# Daughterboard.net
KiCad netlist of a schematic drawn in Altium Designer
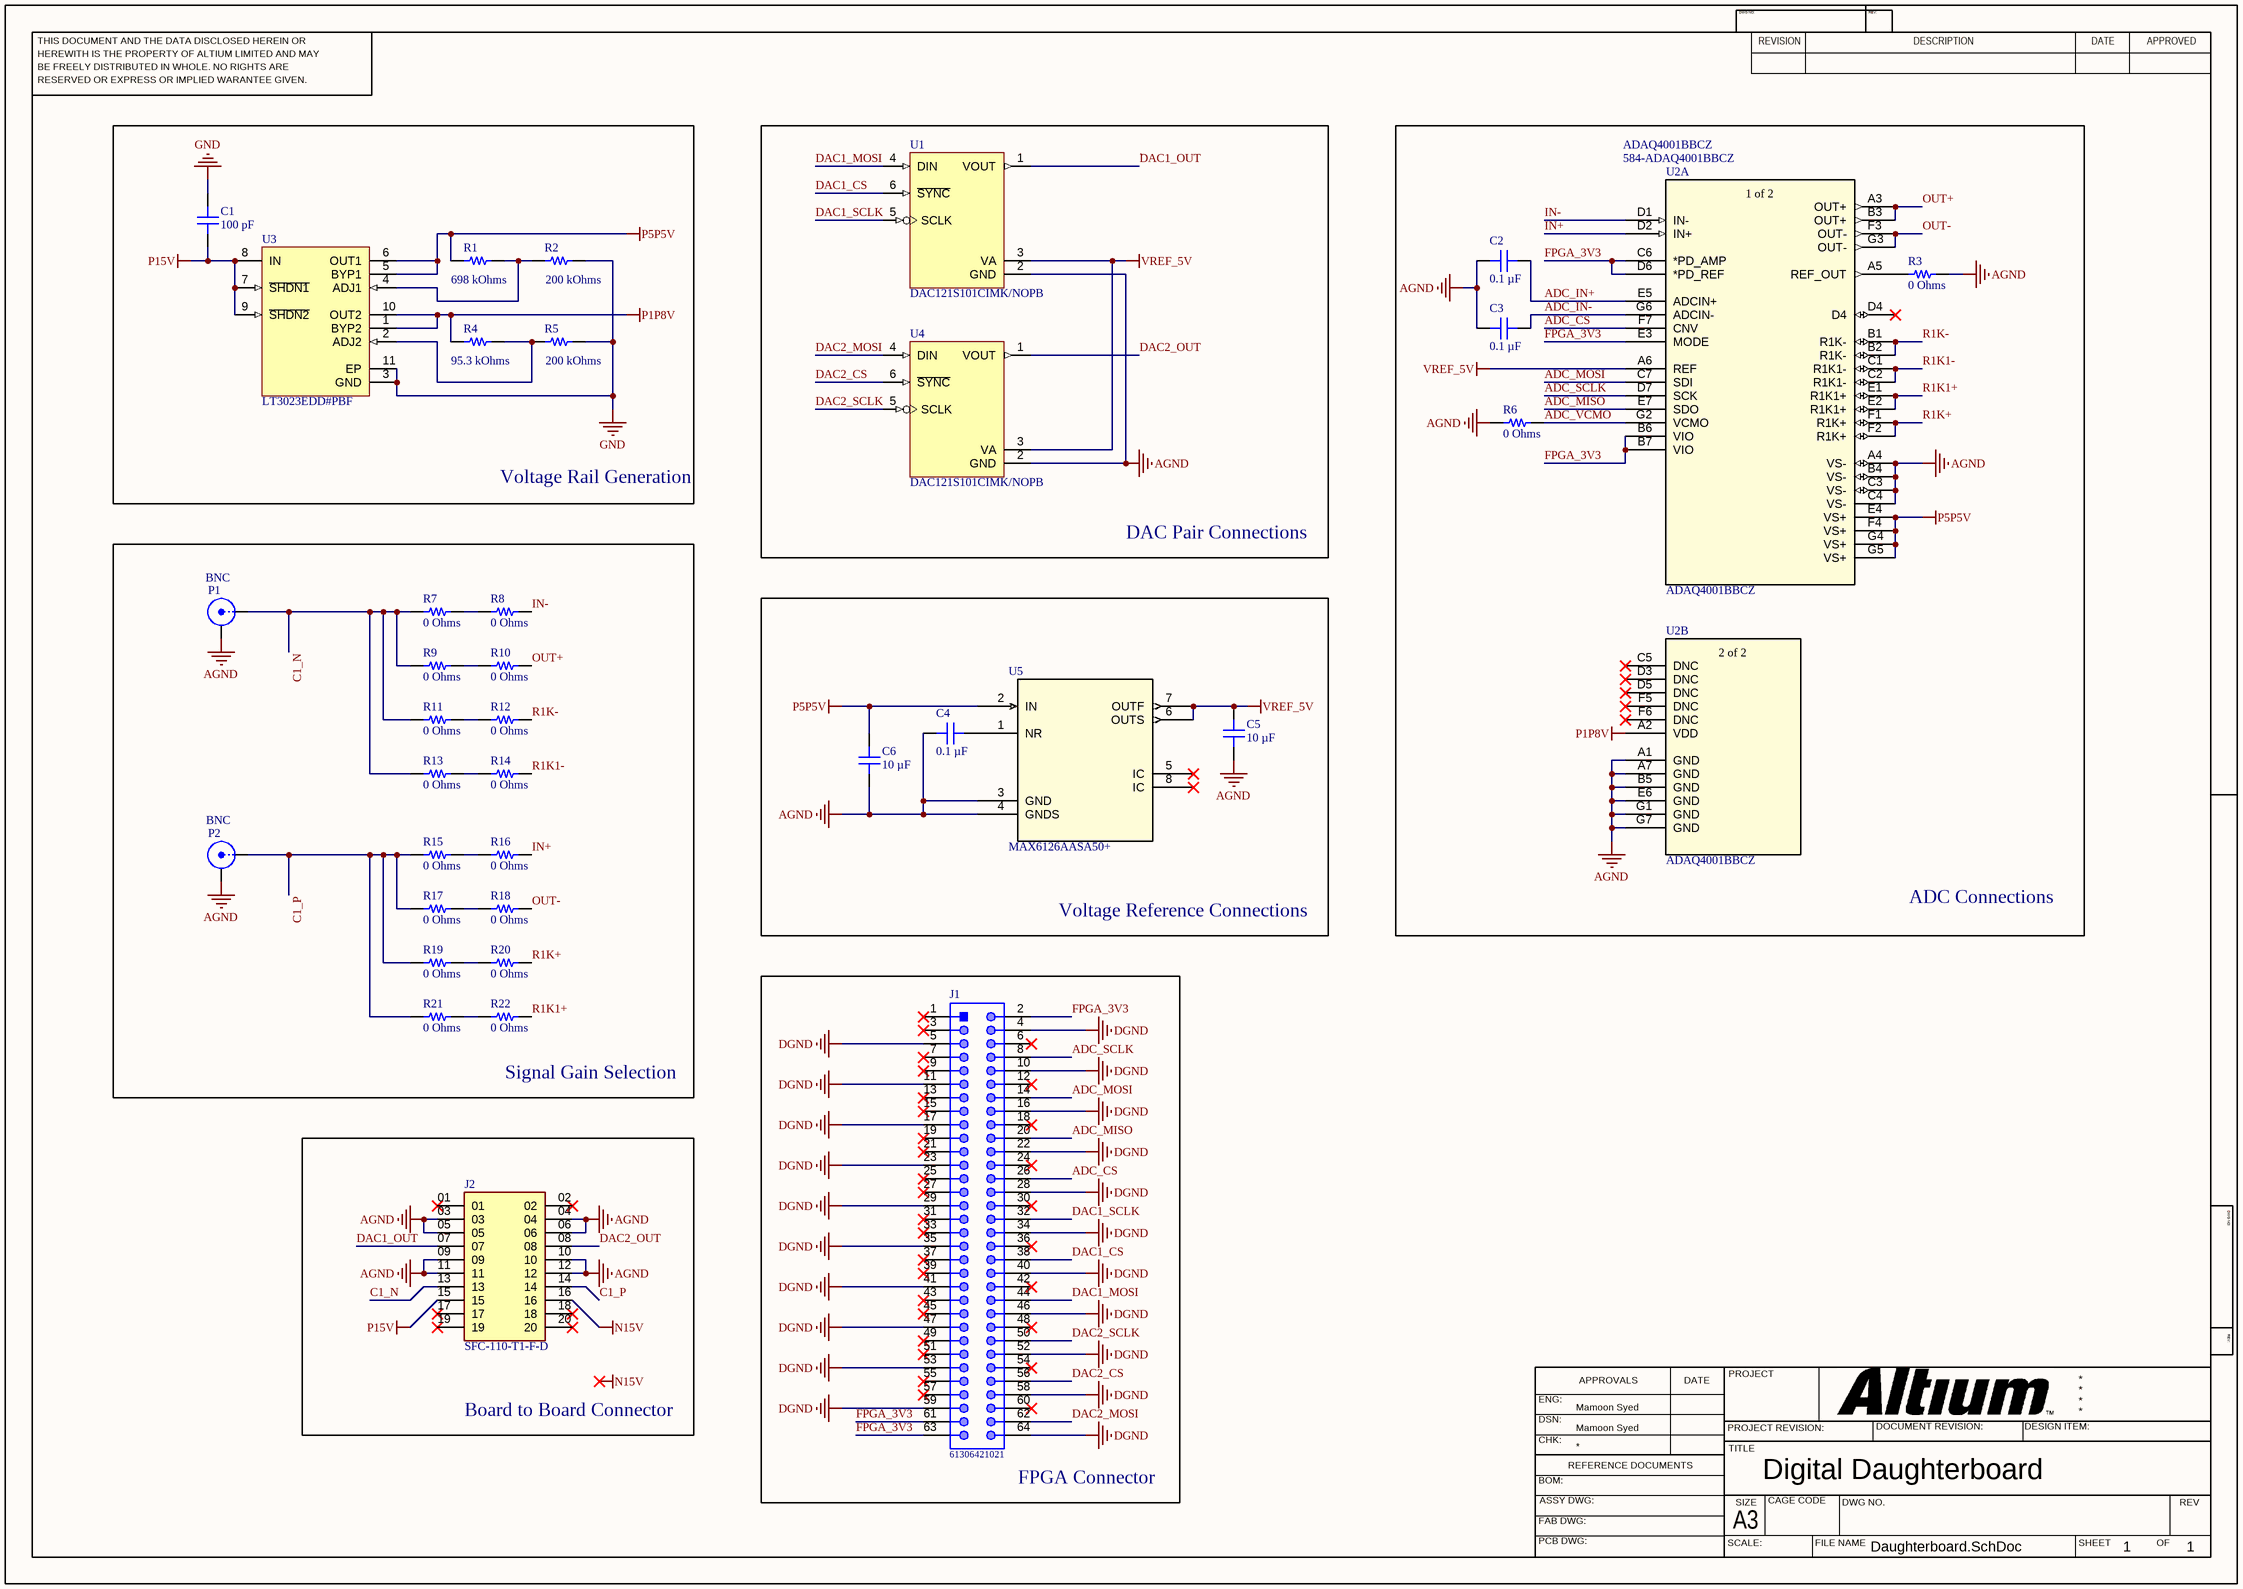
[diagram p0: Daughterboard.SchDoc]

(export (version "E")
  (design (tool "Eeschema 10.0.6"))
  (components
    (comp (ref "C1")
      (value "100 pF")
      (footprint "CAP 0603_1608")
      (description "CAP CER 100PF 50V C0G/NP0 0603")
      (fields (field (name "PART NUMBER") "C0603C101K5GACAUTO") (field (name "MANUFACTURER") "KEMET"))
      (libsource (lib "Celestial Altium Library - altium_library") (part "Capacitor"))
    )
    (comp (ref "C2")
      (value "0.1 µF")
      (footprint "CAP 0603_1608")
      (description "CAP CER 0.1UF 50V X7R 0603")
      (fields (field (name "PART NUMBER") "C0603C104K5RAC7411") (field (name "MANUFACTURER") "KEMET"))
      (libsource (lib "Celestial Altium Library - altium_library") (part "Capacitor"))
    )
    (comp (ref "C3")
      (value "0.1 µF")
      (footprint "CAP 0603_1608")
      (description "CAP CER 0.1UF 50V X7R 0603")
      (fields (field (name "PART NUMBER") "C0603C104K5RAC7411") (field (name "MANUFACTURER") "KEMET"))
      (libsource (lib "Celestial Altium Library - altium_library") (part "Capacitor"))
    )
    (comp (ref "C4")
      (value "0.1 µF")
      (footprint "CAP 0603_1608")
      (description "CAP CER 0.1UF 50V X7R 0603")
      (fields (field (name "PART NUMBER") "C0603C104K5RAC7411") (field (name "MANUFACTURER") "KEMET"))
      (libsource (lib "Celestial Altium Library - altium_library") (part "Capacitor"))
    )
    (comp (ref "C5")
      (value "10 µF")
      (footprint "CAP 0603_1608")
      (description "CAP CER 10UF 6.3V X5R 0603")
      (fields
        (field (name "PART NUMBER") "GRM188R60J106ME47D")
        (field (name "MANUFACTURER") "Murata Electronics")
      )
      (libsource (lib "Celestial Altium Library - altium_library") (part "Capacitor"))
    )
    (comp (ref "C6")
      (value "10 µF")
      (footprint "CAP 0603_1608")
      (description "CAP CER 10UF 6.3V X5R 0603")
      (fields
        (field (name "PART NUMBER") "GRM188R60J106ME47D")
        (field (name "MANUFACTURER") "Murata Electronics")
      )
      (libsource (lib "Celestial Altium Library - altium_library") (part "Capacitor"))
    )
    (comp (ref "J1")
      (value "61306421021")
      (footprint "61306421021")
      (description "THT Angled Pin Header WR-PHD, Pitch 2.54 mm, Dual Row, 64 pins")
      (fields (field (name "MANUFACTURER") "Wurth Elektronik") (field (name "PUBLISHER") "WurthElektronik"))
      (libsource (lib "Altium Content Vault") (part "WE-CN-2P-M-R64"))
    )
    (comp (ref "J2")
      (value "SFC-110-T1-F-D")
      (footprint "SAMTEC_SFC-110-T1-F-D")
      (libsource (lib "SFC-110-T1-F-D") (part "SFC-110-T1-F-D"))
    )
    (comp (ref "P1")
      (value "BNC")
      (footprint "BNC_RA CON")
      (description "BNC Elbow Connector")
      (fields (field (name "PUBLISHER") "Altium Limited"))
      (libsource (lib "Miscellaneous Connectors") (part "BNC"))
    )
    (comp (ref "P2")
      (value "BNC")
      (footprint "BNC_RA CON")
      (description "BNC Elbow Connector")
      (fields (field (name "PUBLISHER") "Altium Limited"))
      (libsource (lib "Miscellaneous Connectors") (part "BNC"))
    )
    (comp (ref "R1")
      (value "698 kOhms")
      (footprint "RES 0603_1608")
      (description "RES 698K OHM 1% 1/10W 0603")
      (fields (field (name "PART NUMBER") "RC0603FR-07698KL") (field (name "MANUFACTURER") "Yageo"))
      (libsource (lib "Celestial Altium Library - altium_library") (part "Resistor"))
    )
    (comp (ref "R2")
      (value "200 kOhms")
      (footprint "RES 0603_1608")
      (description "RES 200K OHM 5% 1/10W 0603")
      (fields
        (field (name "PART NUMBER") "RK73B1JTTD204J")
        (field (name "MANUFACTURER") "KOA Speer Electronics, Inc.")
      )
      (libsource (lib "Celestial Altium Library - altium_library") (part "Resistor"))
    )
    (comp (ref "R3")
      (value "0 Ohms")
      (footprint "RES 0603_1608")
      (description "RES SMD 0 OHM JUMPER 1/10W 0603")
      (fields (field (name "PART NUMBER") "AC0603JR-070RL") (field (name "MANUFACTURER") "Yageo"))
      (libsource (lib "Celestial Altium Library - altium_library") (part "Resistor"))
    )
    (comp (ref "R4")
      (value "95.3 kOhms")
      (footprint "RES 0603_1608")
      (description "RES 95.3K OHM 1% 1/10W 0603")
      (fields (field (name "PART NUMBER") "RC0603FR-0795K3L") (field (name "MANUFACTURER") "Yageo"))
      (libsource (lib "Celestial Altium Library - altium_library") (part "Resistor"))
    )
    (comp (ref "R5")
      (value "200 kOhms")
      (footprint "RES 0603_1608")
      (description "RES 200K OHM 5% 1/10W 0603")
      (fields
        (field (name "PART NUMBER") "RK73B1JTTD204J")
        (field (name "MANUFACTURER") "KOA Speer Electronics, Inc.")
      )
      (libsource (lib "Celestial Altium Library - altium_library") (part "Resistor"))
    )
    (comp (ref "R6")
      (value "0 Ohms")
      (footprint "RES 0603_1608")
      (description "RES SMD 0 OHM JUMPER 1/10W 0603")
      (fields (field (name "PART NUMBER") "AC0603JR-070RL") (field (name "MANUFACTURER") "Yageo"))
      (libsource (lib "Celestial Altium Library - altium_library") (part "Resistor"))
    )
    (comp (ref "R7")
      (value "0 Ohms")
      (footprint "RES 0603_1608")
      (description "RES SMD 0 OHM JUMPER 1/10W 0603")
      (fields (field (name "PART NUMBER") "AC0603JR-070RL") (field (name "MANUFACTURER") "Yageo"))
      (libsource (lib "Celestial Altium Library - altium_library") (part "Resistor"))
    )
    (comp (ref "R8")
      (value "0 Ohms")
      (footprint "RES 0603_1608")
      (description "RES SMD 0 OHM JUMPER 1/10W 0603")
      (fields (field (name "PART NUMBER") "AC0603JR-070RL") (field (name "MANUFACTURER") "Yageo"))
      (libsource (lib "Celestial Altium Library - altium_library") (part "Resistor"))
    )
    (comp (ref "R9")
      (value "0 Ohms")
      (footprint "RES 0603_1608")
      (description "RES SMD 0 OHM JUMPER 1/10W 0603")
      (fields (field (name "PART NUMBER") "AC0603JR-070RL") (field (name "MANUFACTURER") "Yageo"))
      (libsource (lib "Celestial Altium Library - altium_library") (part "Resistor"))
    )
    (comp (ref "R10")
      (value "0 Ohms")
      (footprint "RES 0603_1608")
      (description "RES SMD 0 OHM JUMPER 1/10W 0603")
      (fields (field (name "PART NUMBER") "AC0603JR-070RL") (field (name "MANUFACTURER") "Yageo"))
      (libsource (lib "Celestial Altium Library - altium_library") (part "Resistor"))
    )
    (comp (ref "R11")
      (value "0 Ohms")
      (footprint "RES 0603_1608")
      (description "RES SMD 0 OHM JUMPER 1/10W 0603")
      (fields (field (name "PART NUMBER") "AC0603JR-070RL") (field (name "MANUFACTURER") "Yageo"))
      (libsource (lib "Celestial Altium Library - altium_library") (part "Resistor"))
    )
    (comp (ref "R12")
      (value "0 Ohms")
      (footprint "RES 0603_1608")
      (description "RES SMD 0 OHM JUMPER 1/10W 0603")
      (fields (field (name "PART NUMBER") "AC0603JR-070RL") (field (name "MANUFACTURER") "Yageo"))
      (libsource (lib "Celestial Altium Library - altium_library") (part "Resistor"))
    )
    (comp (ref "R13")
      (value "0 Ohms")
      (footprint "RES 0603_1608")
      (description "RES SMD 0 OHM JUMPER 1/10W 0603")
      (fields (field (name "PART NUMBER") "AC0603JR-070RL") (field (name "MANUFACTURER") "Yageo"))
      (libsource (lib "Celestial Altium Library - altium_library") (part "Resistor"))
    )
    (comp (ref "R14")
      (value "0 Ohms")
      (footprint "RES 0603_1608")
      (description "RES SMD 0 OHM JUMPER 1/10W 0603")
      (fields (field (name "PART NUMBER") "AC0603JR-070RL") (field (name "MANUFACTURER") "Yageo"))
      (libsource (lib "Celestial Altium Library - altium_library") (part "Resistor"))
    )
    (comp (ref "R15")
      (value "0 Ohms")
      (footprint "RES 0603_1608")
      (description "RES SMD 0 OHM JUMPER 1/10W 0603")
      (fields (field (name "PART NUMBER") "AC0603JR-070RL") (field (name "MANUFACTURER") "Yageo"))
      (libsource (lib "Celestial Altium Library - altium_library") (part "Resistor"))
    )
    (comp (ref "R16")
      (value "0 Ohms")
      (footprint "RES 0603_1608")
      (description "RES SMD 0 OHM JUMPER 1/10W 0603")
      (fields (field (name "PART NUMBER") "AC0603JR-070RL") (field (name "MANUFACTURER") "Yageo"))
      (libsource (lib "Celestial Altium Library - altium_library") (part "Resistor"))
    )
    (comp (ref "R17")
      (value "0 Ohms")
      (footprint "RES 0603_1608")
      (description "RES SMD 0 OHM JUMPER 1/10W 0603")
      (fields (field (name "PART NUMBER") "AC0603JR-070RL") (field (name "MANUFACTURER") "Yageo"))
      (libsource (lib "Celestial Altium Library - altium_library") (part "Resistor"))
    )
    (comp (ref "R18")
      (value "0 Ohms")
      (footprint "RES 0603_1608")
      (description "RES SMD 0 OHM JUMPER 1/10W 0603")
      (fields (field (name "PART NUMBER") "AC0603JR-070RL") (field (name "MANUFACTURER") "Yageo"))
      (libsource (lib "Celestial Altium Library - altium_library") (part "Resistor"))
    )
    (comp (ref "R19")
      (value "0 Ohms")
      (footprint "RES 0603_1608")
      (description "RES SMD 0 OHM JUMPER 1/10W 0603")
      (fields (field (name "PART NUMBER") "AC0603JR-070RL") (field (name "MANUFACTURER") "Yageo"))
      (libsource (lib "Celestial Altium Library - altium_library") (part "Resistor"))
    )
    (comp (ref "R20")
      (value "0 Ohms")
      (footprint "RES 0603_1608")
      (description "RES SMD 0 OHM JUMPER 1/10W 0603")
      (fields (field (name "PART NUMBER") "AC0603JR-070RL") (field (name "MANUFACTURER") "Yageo"))
      (libsource (lib "Celestial Altium Library - altium_library") (part "Resistor"))
    )
    (comp (ref "R21")
      (value "0 Ohms")
      (footprint "RES 0603_1608")
      (description "RES SMD 0 OHM JUMPER 1/10W 0603")
      (fields (field (name "PART NUMBER") "AC0603JR-070RL") (field (name "MANUFACTURER") "Yageo"))
      (libsource (lib "Celestial Altium Library - altium_library") (part "Resistor"))
    )
    (comp (ref "R22")
      (value "0 Ohms")
      (footprint "RES 0603_1608")
      (description "RES SMD 0 OHM JUMPER 1/10W 0603")
      (fields (field (name "PART NUMBER") "AC0603JR-070RL") (field (name "MANUFACTURER") "Yageo"))
      (libsource (lib "Celestial Altium Library - altium_library") (part "Resistor"))
    )
    (comp (ref "U1")
      (value "DAC121S101CIMK/NOPB")
      (footprint "MK06A_N")
      (description "12-Bit Micro Power, RRO Digital-to-Analog Converter, 6-pin Tiny SOT23, Pb-Free")
      (fields (field (name "MANUFACTURER") "National Semiconductor"))
      (libsource (lib "Altium Content Vault") (part "CON-DAC-DAC121S101-6"))
    )
    (comp (ref "U2")
      (value "ADAQ4001BBCZ")
      (footprint "BGA49_ADAQ4001BBCZ_ADI")
      (description "Analog Devices ADAQ4001 - 16-Bit Sequential Approximation ADC")
      (fields
        (field (name "SUPPLIER PART NUMBER 1") "584-ADAQ4001BBCZ")
        (field (name "SUPPLIER PART NUMBER 2") "ADAQ4001BBCZ")
        (field (name "COPYRIGHT") "Copyright (C) 2022 Ultra Librarian. All rights reserved.")
      )
      (libsource (lib "ADAQ4001BBCZ") (part "ADAQ4001BBCZ"))
    )
    (comp (ref "U3")
      (value "LT3023EDD#PBF")
      (footprint "LT-DD-10_V")
      (fields (field (name "MANUFACTURER") "Linear Technology"))
      (libsource (lib "Altium Content Vault") (part "LT-LT3023-X-10-X"))
    )
    (comp (ref "U4")
      (value "DAC121S101CIMK/NOPB")
      (footprint "MK06A_N")
      (description "12-Bit Micro Power, RRO Digital-to-Analog Converter, 6-pin Tiny SOT23, Pb-Free")
      (fields (field (name "MANUFACTURER") "National Semiconductor"))
      (libsource (lib "Altium Content Vault") (part "CON-DAC-DAC121S101-6"))
    )
    (comp (ref "U5")
      (value "MAX6126AASA50+")
      (footprint "21-0041B_8")
      (description "MAX6126AASA50+ Voltage Reference")
      (fields (field (name "COPYRIGHT") "Copyright (C) 2022 Ultra Librarian. All rights reserved."))
      (libsource (lib "MAX6126AASA50&plus_") (part "MAX6126AASA50+"))
    )
  )
  (nets
    (net (code "1") (name "/ADC_CS") (class "Default")
      (node (ref "J1") (pin "26") (pinfunction "26_26") (pintype "passive"))
      (node (ref "U2") (pin "F7") (pinfunction "CNV_F7") (pintype "passive"))
    )
    (net (code "2") (name "/ADC_IN+") (class "Default")
      (node (ref "C2") (pin "2") (pinfunction "2_2") (pintype "passive"))
      (node (ref "U2") (pin "E5") (pinfunction "ADCIN+_E5") (pintype "passive"))
    )
    (net (code "3") (name "/ADC_IN-") (class "Default")
      (node (ref "C3") (pin "2") (pinfunction "2_2") (pintype "passive"))
      (node (ref "U2") (pin "G6") (pinfunction "ADCIN-_G6") (pintype "passive"))
    )
    (net (code "4") (name "/ADC_MISO") (class "Default")
      (node (ref "J1") (pin "20") (pinfunction "20_20") (pintype "passive"))
      (node (ref "U2") (pin "E7") (pinfunction "SDO_E7") (pintype "passive"))
    )
    (net (code "5") (name "/ADC_MOSI") (class "Default")
      (node (ref "J1") (pin "14") (pinfunction "14_14") (pintype "passive"))
      (node (ref "U2") (pin "C7") (pinfunction "SDI_C7") (pintype "passive"))
    )
    (net (code "6") (name "/ADC_SCLK") (class "Default")
      (node (ref "J1") (pin "8") (pinfunction "8_8") (pintype "passive"))
      (node (ref "U2") (pin "D7") (pinfunction "SCK_D7") (pintype "passive"))
    )
    (net (code "7") (name "/ADC_VCMO") (class "Default")
      (node (ref "R6") (pin "2") (pinfunction "2_2") (pintype "passive"))
      (node (ref "U2") (pin "G2") (pinfunction "VCMO_G2") (pintype "passive"))
    )
    (net (code "8") (name "/C1_N") (class "Default")
      (node (ref "J2") (pin "13") (pinfunction "13_13") (pintype "passive"))
      (node (ref "P1") (pin "1") (pinfunction "X_1") (pintype "passive"))
      (node (ref "R11") (pin "1") (pinfunction "1_1") (pintype "passive"))
      (node (ref "R13") (pin "1") (pinfunction "1_1") (pintype "passive"))
      (node (ref "R7") (pin "1") (pinfunction "1_1") (pintype "passive"))
      (node (ref "R9") (pin "1") (pinfunction "1_1") (pintype "passive"))
    )
    (net (code "9") (name "/C1_P") (class "Default")
      (node (ref "J2") (pin "14") (pinfunction "14_14") (pintype "passive"))
      (node (ref "P2") (pin "1") (pinfunction "X_1") (pintype "passive"))
      (node (ref "R15") (pin "1") (pinfunction "1_1") (pintype "passive"))
      (node (ref "R17") (pin "1") (pinfunction "1_1") (pintype "passive"))
      (node (ref "R19") (pin "1") (pinfunction "1_1") (pintype "passive"))
      (node (ref "R21") (pin "1") (pinfunction "1_1") (pintype "passive"))
    )
    (net (code "10") (name "/DAC1_CS") (class "Default")
      (node (ref "J1") (pin "38") (pinfunction "38_38") (pintype "passive"))
      (node (ref "U1") (pin "6") (pinfunction "~{SYNC}_6") (pintype "input"))
    )
    (net (code "11") (name "/DAC1_MOSI") (class "Default")
      (node (ref "J1") (pin "44") (pinfunction "44_44") (pintype "passive"))
      (node (ref "U1") (pin "4") (pinfunction "DIN_4") (pintype "input"))
    )
    (net (code "12") (name "/DAC1_OUT") (class "Default")
      (node (ref "J2") (pin "07") (pinfunction "07_07") (pintype "passive"))
      (node (ref "U1") (pin "1") (pinfunction "VOUT_1") (pintype "output"))
    )
    (net (code "13") (name "/DAC1_SCLK") (class "Default")
      (node (ref "J1") (pin "32") (pinfunction "32_32") (pintype "passive"))
      (node (ref "U1") (pin "5") (pinfunction "SCLK_5") (pintype "input"))
    )
    (net (code "14") (name "/DAC2_CS") (class "Default")
      (node (ref "J1") (pin "56") (pinfunction "56_56") (pintype "passive"))
      (node (ref "U4") (pin "6") (pinfunction "~{SYNC}_6") (pintype "input"))
    )
    (net (code "15") (name "/DAC2_MOSI") (class "Default")
      (node (ref "J1") (pin "62") (pinfunction "62_62") (pintype "passive"))
      (node (ref "U4") (pin "4") (pinfunction "DIN_4") (pintype "input"))
    )
    (net (code "16") (name "/DAC2_OUT") (class "Default")
      (node (ref "J2") (pin "08") (pinfunction "08_08") (pintype "passive"))
      (node (ref "U4") (pin "1") (pinfunction "VOUT_1") (pintype "output"))
    )
    (net (code "17") (name "/DAC2_SCLK") (class "Default")
      (node (ref "J1") (pin "50") (pinfunction "50_50") (pintype "passive"))
      (node (ref "U4") (pin "5") (pinfunction "SCLK_5") (pintype "input"))
    )
    (net (code "18") (name "/FPGA_3V3") (class "Default")
      (node (ref "J1") (pin "2") (pinfunction "2_2") (pintype "passive"))
      (node (ref "J1") (pin "61") (pinfunction "61_61") (pintype "passive"))
      (node (ref "J1") (pin "63") (pinfunction "63_63") (pintype "passive"))
      (node (ref "U2") (pin "B6") (pinfunction "VIO_B6") (pintype "passive"))
      (node (ref "U2") (pin "B7") (pinfunction "VIO_B7") (pintype "passive"))
      (node (ref "U2") (pin "C6") (pinfunction "*PD_AMP_C6") (pintype "passive"))
      (node (ref "U2") (pin "D6") (pinfunction "*PD_REF_D6") (pintype "passive"))
      (node (ref "U2") (pin "E3") (pinfunction "MODE_E3") (pintype "passive"))
    )
    (net (code "19") (name "/IN+") (class "Default")
      (node (ref "R16") (pin "2") (pinfunction "2_2") (pintype "passive"))
      (node (ref "U2") (pin "D2") (pinfunction "IN+_D2") (pintype "input"))
    )
    (net (code "20") (name "/IN-") (class "Default")
      (node (ref "R8") (pin "2") (pinfunction "2_2") (pintype "passive"))
      (node (ref "U2") (pin "D1") (pinfunction "IN-_D1") (pintype "input"))
    )
    (net (code "21") (name "/OUT+") (class "Default")
      (node (ref "R10") (pin "2") (pinfunction "2_2") (pintype "passive"))
      (node (ref "U2") (pin "A3") (pinfunction "OUT+_A3") (pintype "output"))
      (node (ref "U2") (pin "B3") (pinfunction "OUT+_B3") (pintype "output"))
    )
    (net (code "22") (name "/OUT-") (class "Default")
      (node (ref "R18") (pin "2") (pinfunction "2_2") (pintype "passive"))
      (node (ref "U2") (pin "F3") (pinfunction "OUT-_F3") (pintype "output"))
      (node (ref "U2") (pin "G3") (pinfunction "OUT-_G3") (pintype "output"))
    )
    (net (code "23") (name "/R1K+") (class "Default")
      (node (ref "R20") (pin "2") (pinfunction "2_2") (pintype "passive"))
      (node (ref "U2") (pin "F1") (pinfunction "R1K+_F1") (pintype "bidirectional"))
      (node (ref "U2") (pin "F2") (pinfunction "R1K+_F2") (pintype "bidirectional"))
    )
    (net (code "24") (name "/R1K-") (class "Default")
      (node (ref "R12") (pin "2") (pinfunction "2_2") (pintype "passive"))
      (node (ref "U2") (pin "B1") (pinfunction "R1K-_B1") (pintype "bidirectional"))
      (node (ref "U2") (pin "B2") (pinfunction "R1K-_B2") (pintype "bidirectional"))
    )
    (net (code "25") (name "/R1K1+") (class "Default")
      (node (ref "R22") (pin "2") (pinfunction "2_2") (pintype "passive"))
      (node (ref "U2") (pin "E1") (pinfunction "R1K1+_E1") (pintype "bidirectional"))
      (node (ref "U2") (pin "E2") (pinfunction "R1K1+_E2") (pintype "bidirectional"))
    )
    (net (code "26") (name "/R1K1-") (class "Default")
      (node (ref "R14") (pin "2") (pinfunction "2_2") (pintype "passive"))
      (node (ref "U2") (pin "C1") (pinfunction "R1K1-_C1") (pintype "bidirectional"))
      (node (ref "U2") (pin "C2") (pinfunction "R1K1-_C2") (pintype "bidirectional"))
    )
    (net (code "27") (name "AGND") (class "Default")
      (node (ref "C2") (pin "1") (pinfunction "1_1") (pintype "passive"))
      (node (ref "C3") (pin "1") (pinfunction "1_1") (pintype "passive"))
      (node (ref "C4") (pin "1") (pinfunction "1_1") (pintype "passive"))
      (node (ref "C5") (pin "1") (pinfunction "1_1") (pintype "passive"))
      (node (ref "C6") (pin "1") (pinfunction "1_1") (pintype "passive"))
      (node (ref "J2") (pin "03") (pinfunction "03_03") (pintype "passive"))
      (node (ref "J2") (pin "04") (pinfunction "04_04") (pintype "passive"))
      (node (ref "J2") (pin "05") (pinfunction "05_05") (pintype "passive"))
      (node (ref "J2") (pin "06") (pinfunction "06_06") (pintype "passive"))
      (node (ref "J2") (pin "09") (pinfunction "09_09") (pintype "passive"))
      (node (ref "J2") (pin "10") (pinfunction "10_10") (pintype "passive"))
      (node (ref "J2") (pin "11") (pinfunction "11_11") (pintype "passive"))
      (node (ref "J2") (pin "12") (pinfunction "12_12") (pintype "passive"))
      (node (ref "P1") (pin "2") (pinfunction "Y_2") (pintype "passive"))
      (node (ref "P2") (pin "2") (pinfunction "Y_2") (pintype "passive"))
      (node (ref "R3") (pin "2") (pinfunction "2_2") (pintype "passive"))
      (node (ref "R6") (pin "1") (pinfunction "1_1") (pintype "passive"))
      (node (ref "U1") (pin "2") (pinfunction "GND_2") (pintype "power_in"))
      (node (ref "U2") (pin "A1") (pinfunction "GND_A1") (pintype "passive"))
      (node (ref "U2") (pin "A4") (pinfunction "VS-_A4") (pintype "bidirectional"))
      (node (ref "U2") (pin "A7") (pinfunction "GND_A7") (pintype "passive"))
      (node (ref "U2") (pin "B4") (pinfunction "VS-_B4") (pintype "bidirectional"))
      (node (ref "U2") (pin "B5") (pinfunction "GND_B5") (pintype "passive"))
      (node (ref "U2") (pin "C3") (pinfunction "VS-_C3") (pintype "bidirectional"))
      (node (ref "U2") (pin "C4") (pinfunction "VS-_C4") (pintype "passive"))
      (node (ref "U2") (pin "E6") (pinfunction "GND_E6") (pintype "passive"))
      (node (ref "U2") (pin "G1") (pinfunction "GND_G1") (pintype "passive"))
      (node (ref "U2") (pin "G7") (pinfunction "GND_G7") (pintype "passive"))
      (node (ref "U4") (pin "2") (pinfunction "GND_2") (pintype "power_in"))
      (node (ref "U5") (pin "3") (pinfunction "GND_3") (pintype "power_in"))
      (node (ref "U5") (pin "4") (pinfunction "GNDS_4") (pintype "power_in"))
    )
    (net (code "28") (name "DGND") (class "Default")
      (node (ref "J1") (pin "10") (pinfunction "10_10") (pintype "passive"))
      (node (ref "J1") (pin "11") (pinfunction "11_11") (pintype "passive"))
      (node (ref "J1") (pin "16") (pinfunction "16_16") (pintype "passive"))
      (node (ref "J1") (pin "17") (pinfunction "17_17") (pintype "passive"))
      (node (ref "J1") (pin "22") (pinfunction "22_22") (pintype "passive"))
      (node (ref "J1") (pin "23") (pinfunction "23_23") (pintype "passive"))
      (node (ref "J1") (pin "28") (pinfunction "28_28") (pintype "passive"))
      (node (ref "J1") (pin "29") (pinfunction "29_29") (pintype "passive"))
      (node (ref "J1") (pin "34") (pinfunction "34_34") (pintype "passive"))
      (node (ref "J1") (pin "35") (pinfunction "35_35") (pintype "passive"))
      (node (ref "J1") (pin "4") (pinfunction "4_4") (pintype "passive"))
      (node (ref "J1") (pin "40") (pinfunction "40_40") (pintype "passive"))
      (node (ref "J1") (pin "41") (pinfunction "41_41") (pintype "passive"))
      (node (ref "J1") (pin "46") (pinfunction "46_46") (pintype "passive"))
      (node (ref "J1") (pin "47") (pinfunction "47_47") (pintype "passive"))
      (node (ref "J1") (pin "5") (pinfunction "5_5") (pintype "passive"))
      (node (ref "J1") (pin "52") (pinfunction "52_52") (pintype "passive"))
      (node (ref "J1") (pin "53") (pinfunction "53_53") (pintype "passive"))
      (node (ref "J1") (pin "58") (pinfunction "58_58") (pintype "passive"))
      (node (ref "J1") (pin "59") (pinfunction "59_59") (pintype "passive"))
      (node (ref "J1") (pin "64") (pinfunction "64_64") (pintype "passive"))
    )
    (net (code "29") (name "GND") (class "Default")
      (node (ref "C1") (pin "2") (pinfunction "2_2") (pintype "passive"))
      (node (ref "R2") (pin "2") (pinfunction "2_2") (pintype "passive"))
      (node (ref "R5") (pin "2") (pinfunction "2_2") (pintype "passive"))
      (node (ref "U3") (pin "11") (pinfunction "EP_11") (pintype "power_in"))
      (node (ref "U3") (pin "3") (pinfunction "GND_3") (pintype "power_in"))
    )
    (net (code "30") (name "N15V") (class "Default")
      (node (ref "J2") (pin "16") (pinfunction "16_16") (pintype "passive"))
    )
    (net (code "31") (name "Net-(R7-Pad2)") (class "Default")
      (node (ref "R7") (pin "2") (pinfunction "2_2") (pintype "passive"))
      (node (ref "R8") (pin "1") (pinfunction "1_1") (pintype "passive"))
    )
    (net (code "32") (name "Net-(R10-Pad1)") (class "Default")
      (node (ref "R10") (pin "1") (pinfunction "1_1") (pintype "passive"))
      (node (ref "R9") (pin "2") (pinfunction "2_2") (pintype "passive"))
    )
    (net (code "33") (name "Net-(R11-Pad2)") (class "Default")
      (node (ref "R11") (pin "2") (pinfunction "2_2") (pintype "passive"))
      (node (ref "R12") (pin "1") (pinfunction "1_1") (pintype "passive"))
    )
    (net (code "34") (name "Net-(R13-Pad2)") (class "Default")
      (node (ref "R13") (pin "2") (pinfunction "2_2") (pintype "passive"))
      (node (ref "R14") (pin "1") (pinfunction "1_1") (pintype "passive"))
    )
    (net (code "35") (name "Net-(R15-Pad2)") (class "Default")
      (node (ref "R15") (pin "2") (pinfunction "2_2") (pintype "passive"))
      (node (ref "R16") (pin "1") (pinfunction "1_1") (pintype "passive"))
    )
    (net (code "36") (name "Net-(R17-Pad2)") (class "Default")
      (node (ref "R17") (pin "2") (pinfunction "2_2") (pintype "passive"))
      (node (ref "R18") (pin "1") (pinfunction "1_1") (pintype "passive"))
    )
    (net (code "37") (name "Net-(R19-Pad2)") (class "Default")
      (node (ref "R19") (pin "2") (pinfunction "2_2") (pintype "passive"))
      (node (ref "R20") (pin "1") (pinfunction "1_1") (pintype "passive"))
    )
    (net (code "38") (name "Net-(R21-Pad2)") (class "Default")
      (node (ref "R21") (pin "2") (pinfunction "2_2") (pintype "passive"))
      (node (ref "R22") (pin "1") (pinfunction "1_1") (pintype "passive"))
    )
    (net (code "39") (name "Net-(U2A-REF_OUT)") (class "Default")
      (node (ref "R3") (pin "1") (pinfunction "1_1") (pintype "passive"))
      (node (ref "U2") (pin "A5") (pinfunction "REF_OUT_A5") (pintype "output"))
    )
    (net (code "40") (name "Net-(U3-ADJ1)") (class "Default")
      (node (ref "R1") (pin "2") (pinfunction "2_2") (pintype "passive"))
      (node (ref "R2") (pin "1") (pinfunction "1_1") (pintype "passive"))
      (node (ref "U3") (pin "4") (pinfunction "ADJ1_4") (pintype "input"))
    )
    (net (code "41") (name "Net-(U3-ADJ2)") (class "Default")
      (node (ref "R4") (pin "2") (pinfunction "2_2") (pintype "passive"))
      (node (ref "R5") (pin "1") (pinfunction "1_1") (pintype "passive"))
      (node (ref "U3") (pin "2") (pinfunction "ADJ2_2") (pintype "input"))
    )
    (net (code "42") (name "Net-(U5-NR)") (class "Default")
      (node (ref "C4") (pin "2") (pinfunction "2_2") (pintype "passive"))
      (node (ref "U5") (pin "1") (pinfunction "NR_1") (pintype "passive"))
    )
    (net (code "43") (name "P1P8V") (class "Default")
      (node (ref "R4") (pin "1") (pinfunction "1_1") (pintype "passive"))
      (node (ref "U2") (pin "A2") (pinfunction "VDD_A2") (pintype "power_in"))
      (node (ref "U3") (pin "1") (pinfunction "BYP2_1") (pintype "passive"))
      (node (ref "U3") (pin "10") (pinfunction "OUT2_10") (pintype "power_in"))
    )
    (net (code "44") (name "P5P5V") (class "Default")
      (node (ref "C6") (pin "2") (pinfunction "2_2") (pintype "passive"))
      (node (ref "R1") (pin "1") (pinfunction "1_1") (pintype "passive"))
      (node (ref "U2") (pin "E4") (pinfunction "VS+_E4") (pintype "passive"))
      (node (ref "U2") (pin "F4") (pinfunction "VS+_F4") (pintype "passive"))
      (node (ref "U2") (pin "G4") (pinfunction "VS+_G4") (pintype "passive"))
      (node (ref "U2") (pin "G5") (pinfunction "VS+_G5") (pintype "passive"))
      (node (ref "U3") (pin "5") (pinfunction "BYP1_5") (pintype "passive"))
      (node (ref "U3") (pin "6") (pinfunction "OUT1_6") (pintype "power_in"))
      (node (ref "U5") (pin "2") (pinfunction "IN_2") (pintype "input"))
    )
    (net (code "45") (name "P15V") (class "Default")
      (node (ref "C1") (pin "1") (pinfunction "1_1") (pintype "passive"))
      (node (ref "J2") (pin "15") (pinfunction "15_15") (pintype "passive"))
      (node (ref "U3") (pin "7") (pinfunction "~{SHDN1}_7") (pintype "input"))
      (node (ref "U3") (pin "8") (pinfunction "IN_8") (pintype "power_in"))
      (node (ref "U3") (pin "9") (pinfunction "~{SHDN2}_9") (pintype "input"))
    )
    (net (code "46") (name "VREF_5V") (class "Default")
      (node (ref "C5") (pin "2") (pinfunction "2_2") (pintype "passive"))
      (node (ref "U1") (pin "3") (pinfunction "VA_3") (pintype "power_in"))
      (node (ref "U2") (pin "A6") (pinfunction "REF_A6") (pintype "passive"))
      (node (ref "U4") (pin "3") (pinfunction "VA_3") (pintype "power_in"))
      (node (ref "U5") (pin "6") (pinfunction "OUTS_6") (pintype "output"))
      (node (ref "U5") (pin "7") (pinfunction "OUTF_7") (pintype "output"))
    )
    (net (code "47") (name "unconnected-(J1-Pad1)") (class "Default")
      (node (ref "J1") (pin "1") (pinfunction "1_1") (pintype "passive+no_connect"))
    )
    (net (code "48") (name "unconnected-(J1-Pad3)") (class "Default")
      (node (ref "J1") (pin "3") (pinfunction "3_3") (pintype "passive+no_connect"))
    )
    (net (code "49") (name "unconnected-(J1-Pad6)") (class "Default")
      (node (ref "J1") (pin "6") (pinfunction "6_6") (pintype "passive+no_connect"))
    )
    (net (code "50") (name "unconnected-(J1-Pad7)") (class "Default")
      (node (ref "J1") (pin "7") (pinfunction "7_7") (pintype "passive+no_connect"))
    )
    (net (code "51") (name "unconnected-(J1-Pad9)") (class "Default")
      (node (ref "J1") (pin "9") (pinfunction "9_9") (pintype "passive+no_connect"))
    )
    (net (code "52") (name "unconnected-(J1-Pad12)") (class "Default")
      (node (ref "J1") (pin "12") (pinfunction "12_12") (pintype "passive+no_connect"))
    )
    (net (code "53") (name "unconnected-(J1-Pad13)") (class "Default")
      (node (ref "J1") (pin "13") (pinfunction "13_13") (pintype "passive+no_connect"))
    )
    (net (code "54") (name "unconnected-(J1-Pad15)") (class "Default")
      (node (ref "J1") (pin "15") (pinfunction "15_15") (pintype "passive+no_connect"))
    )
    (net (code "55") (name "unconnected-(J1-Pad18)") (class "Default")
      (node (ref "J1") (pin "18") (pinfunction "18_18") (pintype "passive+no_connect"))
    )
    (net (code "56") (name "unconnected-(J1-Pad19)") (class "Default")
      (node (ref "J1") (pin "19") (pinfunction "19_19") (pintype "passive+no_connect"))
    )
    (net (code "57") (name "unconnected-(J1-Pad21)") (class "Default")
      (node (ref "J1") (pin "21") (pinfunction "21_21") (pintype "passive+no_connect"))
    )
    (net (code "58") (name "unconnected-(J1-Pad24)") (class "Default")
      (node (ref "J1") (pin "24") (pinfunction "24_24") (pintype "passive+no_connect"))
    )
    (net (code "59") (name "unconnected-(J1-Pad25)") (class "Default")
      (node (ref "J1") (pin "25") (pinfunction "25_25") (pintype "passive+no_connect"))
    )
    (net (code "60") (name "unconnected-(J1-Pad27)") (class "Default")
      (node (ref "J1") (pin "27") (pinfunction "27_27") (pintype "passive+no_connect"))
    )
    (net (code "61") (name "unconnected-(J1-Pad30)") (class "Default")
      (node (ref "J1") (pin "30") (pinfunction "30_30") (pintype "passive+no_connect"))
    )
    (net (code "62") (name "unconnected-(J1-Pad31)") (class "Default")
      (node (ref "J1") (pin "31") (pinfunction "31_31") (pintype "passive+no_connect"))
    )
    (net (code "63") (name "unconnected-(J1-Pad33)") (class "Default")
      (node (ref "J1") (pin "33") (pinfunction "33_33") (pintype "passive+no_connect"))
    )
    (net (code "64") (name "unconnected-(J1-Pad36)") (class "Default")
      (node (ref "J1") (pin "36") (pinfunction "36_36") (pintype "passive+no_connect"))
    )
    (net (code "65") (name "unconnected-(J1-Pad37)") (class "Default")
      (node (ref "J1") (pin "37") (pinfunction "37_37") (pintype "passive+no_connect"))
    )
    (net (code "66") (name "unconnected-(J1-Pad39)") (class "Default")
      (node (ref "J1") (pin "39") (pinfunction "39_39") (pintype "passive+no_connect"))
    )
    (net (code "67") (name "unconnected-(J1-Pad42)") (class "Default")
      (node (ref "J1") (pin "42") (pinfunction "42_42") (pintype "passive+no_connect"))
    )
    (net (code "68") (name "unconnected-(J1-Pad43)") (class "Default")
      (node (ref "J1") (pin "43") (pinfunction "43_43") (pintype "passive+no_connect"))
    )
    (net (code "69") (name "unconnected-(J1-Pad45)") (class "Default")
      (node (ref "J1") (pin "45") (pinfunction "45_45") (pintype "passive+no_connect"))
    )
    (net (code "70") (name "unconnected-(J1-Pad48)") (class "Default")
      (node (ref "J1") (pin "48") (pinfunction "48_48") (pintype "passive+no_connect"))
    )
    (net (code "71") (name "unconnected-(J1-Pad49)") (class "Default")
      (node (ref "J1") (pin "49") (pinfunction "49_49") (pintype "passive+no_connect"))
    )
    (net (code "72") (name "unconnected-(J1-Pad51)") (class "Default")
      (node (ref "J1") (pin "51") (pinfunction "51_51") (pintype "passive+no_connect"))
    )
    (net (code "73") (name "unconnected-(J1-Pad54)") (class "Default")
      (node (ref "J1") (pin "54") (pinfunction "54_54") (pintype "passive+no_connect"))
    )
    (net (code "74") (name "unconnected-(J1-Pad55)") (class "Default")
      (node (ref "J1") (pin "55") (pinfunction "55_55") (pintype "passive+no_connect"))
    )
    (net (code "75") (name "unconnected-(J1-Pad57)") (class "Default")
      (node (ref "J1") (pin "57") (pinfunction "57_57") (pintype "passive+no_connect"))
    )
    (net (code "76") (name "unconnected-(J1-Pad60)") (class "Default")
      (node (ref "J1") (pin "60") (pinfunction "60_60") (pintype "passive+no_connect"))
    )
    (net (code "77") (name "unconnected-(J2-Pad01)") (class "Default")
      (node (ref "J2") (pin "01") (pinfunction "01_01") (pintype "passive+no_connect"))
    )
    (net (code "78") (name "unconnected-(J2-Pad02)") (class "Default")
      (node (ref "J2") (pin "02") (pinfunction "02_02") (pintype "passive+no_connect"))
    )
    (net (code "79") (name "unconnected-(J2-Pad17)") (class "Default")
      (node (ref "J2") (pin "17") (pinfunction "17_17") (pintype "passive+no_connect"))
    )
    (net (code "80") (name "unconnected-(J2-Pad18)") (class "Default")
      (node (ref "J2") (pin "18") (pinfunction "18_18") (pintype "passive+no_connect"))
    )
    (net (code "81") (name "unconnected-(J2-Pad19)") (class "Default")
      (node (ref "J2") (pin "19") (pinfunction "19_19") (pintype "passive+no_connect"))
    )
    (net (code "82") (name "unconnected-(J2-Pad20)") (class "Default")
      (node (ref "J2") (pin "20") (pinfunction "20_20") (pintype "passive+no_connect"))
    )
    (net (code "83") (name "unconnected-(U2-PadD4)") (class "Default")
      (node (ref "U2") (pin "D4") (pinfunction "D4_D4") (pintype "bidirectional+no_connect"))
    )
    (net (code "84") (name "unconnected-(U2B-DNC-PadC5)") (class "Default")
      (node (ref "U2") (pin "C5") (pinfunction "DNC_C5") (pintype "passive+no_connect"))
    )
    (net (code "85") (name "unconnected-(U2B-DNC-PadD3)") (class "Default")
      (node (ref "U2") (pin "D3") (pinfunction "DNC_D3") (pintype "passive+no_connect"))
    )
    (net (code "86") (name "unconnected-(U2B-DNC-PadD5)") (class "Default")
      (node (ref "U2") (pin "D5") (pinfunction "DNC_D5") (pintype "passive+no_connect"))
    )
    (net (code "87") (name "unconnected-(U2B-DNC-PadF5)") (class "Default")
      (node (ref "U2") (pin "F5") (pinfunction "DNC_F5") (pintype "passive+no_connect"))
    )
    (net (code "88") (name "unconnected-(U2B-DNC-PadF6)") (class "Default")
      (node (ref "U2") (pin "F6") (pinfunction "DNC_F6") (pintype "passive+no_connect"))
    )
    (net (code "89") (name "unconnected-(U5-IC-Pad5)") (class "Default")
      (node (ref "U5") (pin "5") (pinfunction "IC_5") (pintype "passive+no_connect"))
    )
    (net (code "90") (name "unconnected-(U5-IC-Pad8)") (class "Default")
      (node (ref "U5") (pin "8") (pinfunction "IC_8") (pintype "passive+no_connect"))
    )
  )
)
